# MrBoosty.net
KiCad netlist of a schematic drawn in EAGLE
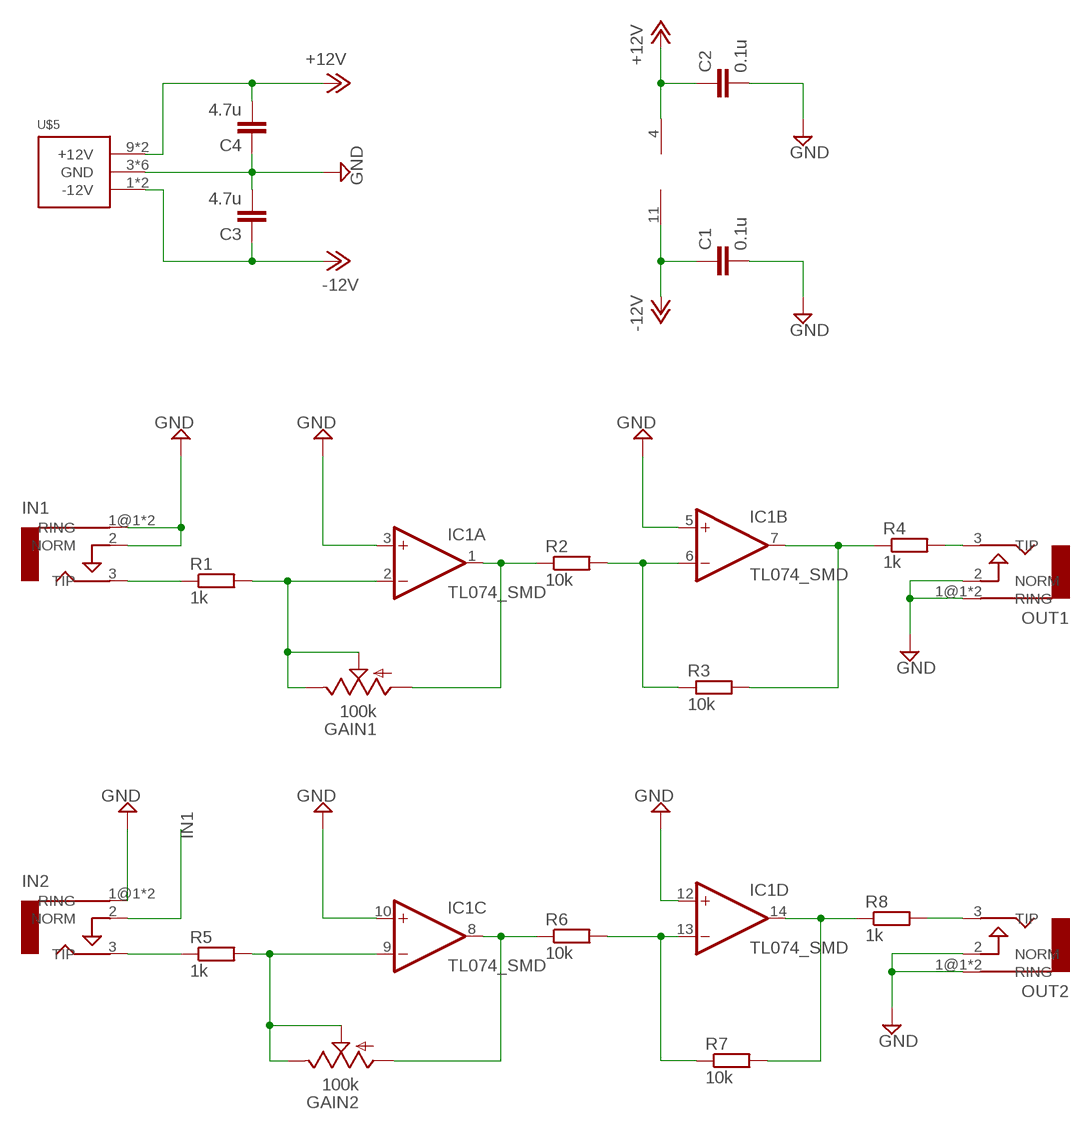
[diagram p0: schematic, sheet 1]

(export (version "E")
  (design (tool "Eeschema 10.0.6"))
  (components
    (comp (ref "C1")
      (value "0.1u")
      (footprint "eagle-import:C0805")
      (libsource (lib "eagle-import") (part "C-EUC0805"))
    )
    (comp (ref "C2")
      (value "0.1u")
      (footprint "eagle-import:C0805")
      (libsource (lib "eagle-import") (part "C-EUC0805"))
    )
    (comp (ref "C3")
      (value "4.7u")
      (footprint "eagle-import:C0805")
      (libsource (lib "eagle-import") (part "C-EUC0805"))
    )
    (comp (ref "C4")
      (value "4.7u")
      (footprint "eagle-import:C0805")
      (libsource (lib "eagle-import") (part "C-EUC0805"))
    )
    (comp (ref "GAIN1")
      (value "100k")
      (footprint "eagle-import:9MM_SNAP-IN_POT")
      (libsource (lib "eagle-import") (part "9MM_SNAP-IN_POT_"))
    )
    (comp (ref "GAIN2")
      (value "100k")
      (footprint "eagle-import:9MM_SNAP-IN_POT")
      (libsource (lib "eagle-import") (part "9MM_SNAP-IN_POT_"))
    )
    (comp (ref "IC1")
      (value "TL074_SMD")
      (footprint "eagle-import:SO14")
      (libsource (lib "eagle-import") (part "TL074_SMD"))
    )
    (comp (ref "IN1")
      (value "AUDIO-JACKERTHENVAR")
      (footprint "eagle-import:ERTHENVAR-JACK")
      (libsource (lib "eagle-import") (part "AUDIO-JACKERTHENVAR"))
    )
    (comp (ref "IN2")
      (value "AUDIO-JACKERTHENVAR")
      (footprint "eagle-import:ERTHENVAR-JACK")
      (libsource (lib "eagle-import") (part "AUDIO-JACKERTHENVAR"))
    )
    (comp (ref "OUT1")
      (value "AUDIO-JACKERTHENVAR")
      (footprint "eagle-import:ERTHENVAR-JACK")
      (libsource (lib "eagle-import") (part "AUDIO-JACKERTHENVAR"))
    )
    (comp (ref "OUT2")
      (value "AUDIO-JACKERTHENVAR")
      (footprint "eagle-import:ERTHENVAR-JACK")
      (libsource (lib "eagle-import") (part "AUDIO-JACKERTHENVAR"))
    )
    (comp (ref "R1")
      (value "1k")
      (footprint "eagle-import:R0805")
      (libsource (lib "eagle-import") (part "R-EU_R0805"))
    )
    (comp (ref "R2")
      (value "10k")
      (footprint "eagle-import:R0805")
      (libsource (lib "eagle-import") (part "R-EU_R0805"))
    )
    (comp (ref "R3")
      (value "10k")
      (footprint "eagle-import:R0805")
      (libsource (lib "eagle-import") (part "R-EU_R0805"))
    )
    (comp (ref "R4")
      (value "1k")
      (footprint "eagle-import:R0805")
      (libsource (lib "eagle-import") (part "R-EU_R0805"))
    )
    (comp (ref "R5")
      (value "1k")
      (footprint "eagle-import:R0805")
      (libsource (lib "eagle-import") (part "R-EU_R0805"))
    )
    (comp (ref "R6")
      (value "10k")
      (footprint "eagle-import:R0805")
      (libsource (lib "eagle-import") (part "R-EU_R0805"))
    )
    (comp (ref "R7")
      (value "10k")
      (footprint "eagle-import:R0805")
      (libsource (lib "eagle-import") (part "R-EU_R0805"))
    )
    (comp (ref "R8")
      (value "1k")
      (footprint "eagle-import:R0805")
      (libsource (lib "eagle-import") (part "R-EU_R0805"))
    )
    (comp (ref "U$5")
      (value "POWER_SIMPLE10")
      (footprint "eagle-import:POWER_10")
      (libsource (lib "eagle-import") (part "POWER_SIMPLE10"))
    )
  )
  (nets
    (net (code "1") (name "+12V") (class "Default")
      (node (ref "C2") (pin "1") (pinfunction "1_1") (pintype "passive"))
      (node (ref "C4") (pin "2") (pinfunction "2_2") (pintype "passive"))
      (node (ref "IC1") (pin "4") (pinfunction "V+_4") (pintype "power_in"))
      (node (ref "U$5") (pin "10") (pinfunction "+12V_10") (pintype "bidirectional"))
      (node (ref "U$5") (pin "9") (pinfunction "+12V_9") (pintype "bidirectional"))
    )
    (net (code "2") (name "-12V") (class "Default")
      (node (ref "C1") (pin "1") (pinfunction "1_1") (pintype "passive"))
      (node (ref "C3") (pin "1") (pinfunction "1_1") (pintype "passive"))
      (node (ref "IC1") (pin "11") (pinfunction "V-_11") (pintype "power_in"))
      (node (ref "U$5") (pin "1") (pinfunction "-12V_1") (pintype "bidirectional"))
      (node (ref "U$5") (pin "2") (pinfunction "-12V_2") (pintype "bidirectional"))
    )
    (net (code "3") (name "/IN1") (class "Default")
      (node (ref "IN1") (pin "3") (pinfunction "TIP_3") (pintype "bidirectional"))
      (node (ref "IN2") (pin "2") (pinfunction "NORM_2") (pintype "bidirectional"))
      (node (ref "R1") (pin "1") (pinfunction "1_1") (pintype "passive"))
    )
    (net (code "4") (name "GND") (class "Default")
      (node (ref "C1") (pin "2") (pinfunction "2_2") (pintype "passive"))
      (node (ref "C2") (pin "2") (pinfunction "2_2") (pintype "passive"))
      (node (ref "C3") (pin "2") (pinfunction "2_2") (pintype "passive"))
      (node (ref "C4") (pin "1") (pinfunction "1_1") (pintype "passive"))
      (node (ref "IC1") (pin "10") (pinfunction "+IN_10") (pintype "input"))
      (node (ref "IC1") (pin "12") (pinfunction "+IN_12") (pintype "input"))
      (node (ref "IC1") (pin "3") (pinfunction "+IN_3") (pintype "input"))
      (node (ref "IC1") (pin "5") (pinfunction "+IN_5") (pintype "input"))
      (node (ref "IN1") (pin "1@1") (pinfunction "RING_1@1") (pintype "bidirectional"))
      (node (ref "IN1") (pin "1@2") (pinfunction "RING_1@2") (pintype "bidirectional"))
      (node (ref "IN1") (pin "2") (pinfunction "NORM_2") (pintype "bidirectional"))
      (node (ref "IN2") (pin "1@1") (pinfunction "RING_1@1") (pintype "bidirectional"))
      (node (ref "IN2") (pin "1@2") (pinfunction "RING_1@2") (pintype "bidirectional"))
      (node (ref "OUT1") (pin "1@1") (pinfunction "RING_1@1") (pintype "bidirectional"))
      (node (ref "OUT1") (pin "1@2") (pinfunction "RING_1@2") (pintype "bidirectional"))
      (node (ref "OUT1") (pin "2") (pinfunction "NORM_2") (pintype "bidirectional"))
      (node (ref "OUT2") (pin "1@1") (pinfunction "RING_1@1") (pintype "bidirectional"))
      (node (ref "OUT2") (pin "1@2") (pinfunction "RING_1@2") (pintype "bidirectional"))
      (node (ref "OUT2") (pin "2") (pinfunction "NORM_2") (pintype "bidirectional"))
      (node (ref "U$5") (pin "3") (pinfunction "GND_3") (pintype "bidirectional"))
      (node (ref "U$5") (pin "4") (pinfunction "GND_4") (pintype "bidirectional"))
      (node (ref "U$5") (pin "5") (pinfunction "GND_5") (pintype "bidirectional"))
      (node (ref "U$5") (pin "6") (pinfunction "GND_6") (pintype "bidirectional"))
      (node (ref "U$5") (pin "7") (pinfunction "GND_7") (pintype "bidirectional"))
      (node (ref "U$5") (pin "8") (pinfunction "GND_8") (pintype "bidirectional"))
    )
    (net (code "5") (name "Net-(GAIN1-A)") (class "Default")
      (node (ref "GAIN1") (pin "1") (pinfunction "A_1") (pintype "passive"))
      (node (ref "IC1") (pin "1") (pinfunction "OUT_1") (pintype "output"))
      (node (ref "R2") (pin "1") (pinfunction "1_1") (pintype "passive"))
    )
    (net (code "6") (name "Net-(GAIN1-E)") (class "Default")
      (node (ref "GAIN1") (pin "2") (pinfunction "S_2") (pintype "passive"))
      (node (ref "GAIN1") (pin "3") (pinfunction "E_3") (pintype "passive"))
      (node (ref "IC1") (pin "2") (pinfunction "-IN_2") (pintype "input"))
      (node (ref "R1") (pin "2") (pinfunction "2_2") (pintype "passive"))
    )
    (net (code "7") (name "Net-(GAIN2-A)") (class "Default")
      (node (ref "GAIN2") (pin "1") (pinfunction "A_1") (pintype "passive"))
      (node (ref "IC1") (pin "8") (pinfunction "OUT_8") (pintype "output"))
      (node (ref "R6") (pin "1") (pinfunction "1_1") (pintype "passive"))
    )
    (net (code "8") (name "Net-(GAIN2-E)") (class "Default")
      (node (ref "GAIN2") (pin "2") (pinfunction "S_2") (pintype "passive"))
      (node (ref "GAIN2") (pin "3") (pinfunction "E_3") (pintype "passive"))
      (node (ref "IC1") (pin "9") (pinfunction "-IN_9") (pintype "input"))
      (node (ref "R5") (pin "2") (pinfunction "2_2") (pintype "passive"))
    )
    (net (code "9") (name "Net-(IC1B--IN)") (class "Default")
      (node (ref "IC1") (pin "6") (pinfunction "-IN_6") (pintype "input"))
      (node (ref "R2") (pin "2") (pinfunction "2_2") (pintype "passive"))
      (node (ref "R3") (pin "1") (pinfunction "1_1") (pintype "passive"))
    )
    (net (code "10") (name "Net-(IC1B-OUT)") (class "Default")
      (node (ref "IC1") (pin "7") (pinfunction "OUT_7") (pintype "output"))
      (node (ref "R3") (pin "2") (pinfunction "2_2") (pintype "passive"))
      (node (ref "R4") (pin "1") (pinfunction "1_1") (pintype "passive"))
    )
    (net (code "11") (name "Net-(IC1D--IN)") (class "Default")
      (node (ref "IC1") (pin "13") (pinfunction "-IN_13") (pintype "input"))
      (node (ref "R6") (pin "2") (pinfunction "2_2") (pintype "passive"))
      (node (ref "R7") (pin "1") (pinfunction "1_1") (pintype "passive"))
    )
    (net (code "12") (name "Net-(IC1D-OUT)") (class "Default")
      (node (ref "IC1") (pin "14") (pinfunction "OUT_14") (pintype "output"))
      (node (ref "R7") (pin "2") (pinfunction "2_2") (pintype "passive"))
      (node (ref "R8") (pin "1") (pinfunction "1_1") (pintype "passive"))
    )
    (net (code "13") (name "Net-(IN2-TIP)") (class "Default")
      (node (ref "IN2") (pin "3") (pinfunction "TIP_3") (pintype "bidirectional"))
      (node (ref "R5") (pin "1") (pinfunction "1_1") (pintype "passive"))
    )
    (net (code "14") (name "Net-(OUT1-TIP)") (class "Default")
      (node (ref "OUT1") (pin "3") (pinfunction "TIP_3") (pintype "bidirectional"))
      (node (ref "R4") (pin "2") (pinfunction "2_2") (pintype "passive"))
    )
    (net (code "15") (name "Net-(OUT2-TIP)") (class "Default")
      (node (ref "OUT2") (pin "3") (pinfunction "TIP_3") (pintype "bidirectional"))
      (node (ref "R8") (pin "2") (pinfunction "2_2") (pintype "passive"))
    )
  )
)
